# TermperatureSens.net
KiCad netlist of a schematic drawn in Altium Designer
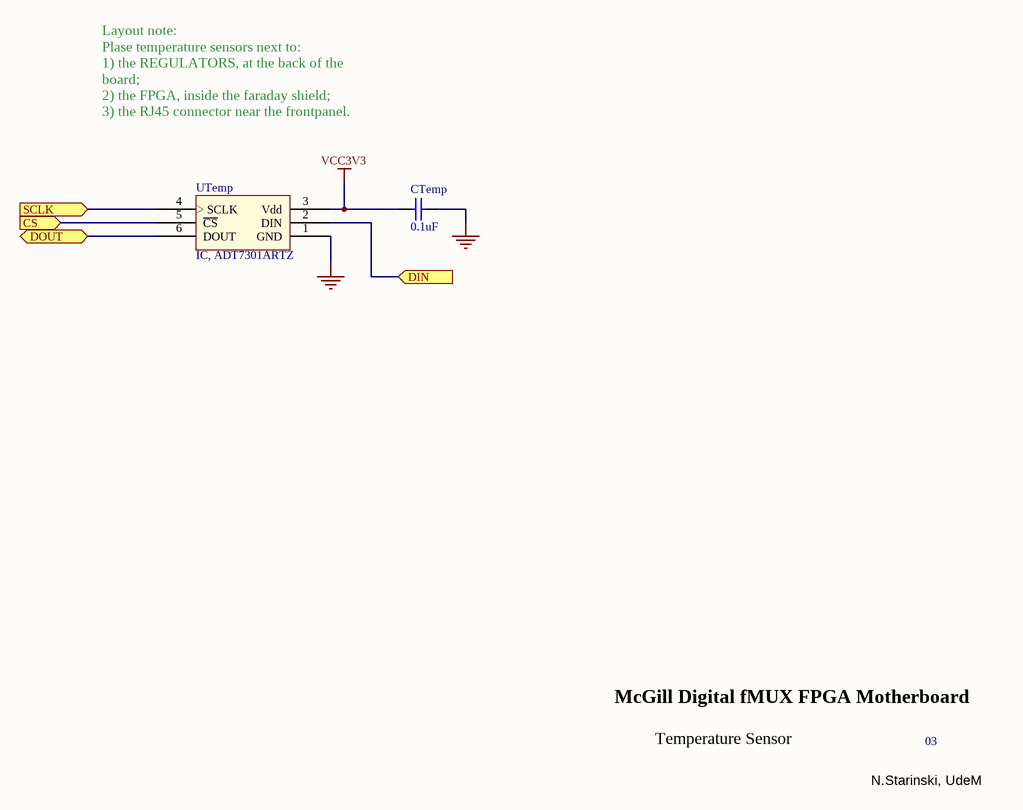
[diagram p0: TermperatureSens.SchDoc]

(export (version "E")
  (design (tool "Eeschema 10.0.6"))
  (components
    (comp (ref "CTemp")
      (value "0.1uF")
      (footprint "CC1608-0603")
      (description "Capacitor (Semiconductor SIM Model)")
      (fields (field (name "PUBLISHER") "Altium Limited"))
      (libsource (lib "Miscellaneous Devices") (part "Cap Semi"))
    )
    (comp (ref "UTemp")
      (value "IC, ADT7301ARTZ")
      (footprint "SO-G6/E2.4")
      (description "Digital Temperature Sensor, 13-Bit, +/-1 Degree Accurate")
      (libsource (lib "TemperatureSensors") (part "ADT7301"))
    )
  )
  (nets
    (net (code "1") (name "/CS") (class "Default")
      (node (ref "UTemp") (pin "5") (pinfunction "~{CS}_5") (pintype "passive"))
    )
    (net (code "2") (name "/DIN") (class "Default")
      (node (ref "UTemp") (pin "2") (pinfunction "DIN_2") (pintype "passive"))
    )
    (net (code "3") (name "/DOUT") (class "Default")
      (node (ref "UTemp") (pin "6") (pinfunction "DOUT_6") (pintype "passive"))
    )
    (net (code "4") (name "/SCLK") (class "Default")
      (node (ref "UTemp") (pin "4") (pinfunction "SCLK_4") (pintype "passive"))
    )
    (net (code "5") (name "GND") (class "Default")
      (node (ref "CTemp") (pin "2") (pinfunction "2_2") (pintype "passive"))
      (node (ref "UTemp") (pin "1") (pinfunction "GND_1") (pintype "power_in"))
    )
    (net (code "6") (name "VCC3V3") (class "Default")
      (node (ref "CTemp") (pin "1") (pinfunction "1_1") (pintype "passive"))
      (node (ref "UTemp") (pin "3") (pinfunction "Vdd_3") (pintype "power_in"))
    )
  )
)
